# Planta_3_sobreamortiguada.net
KiCad netlist of a schematic drawn in EAGLE
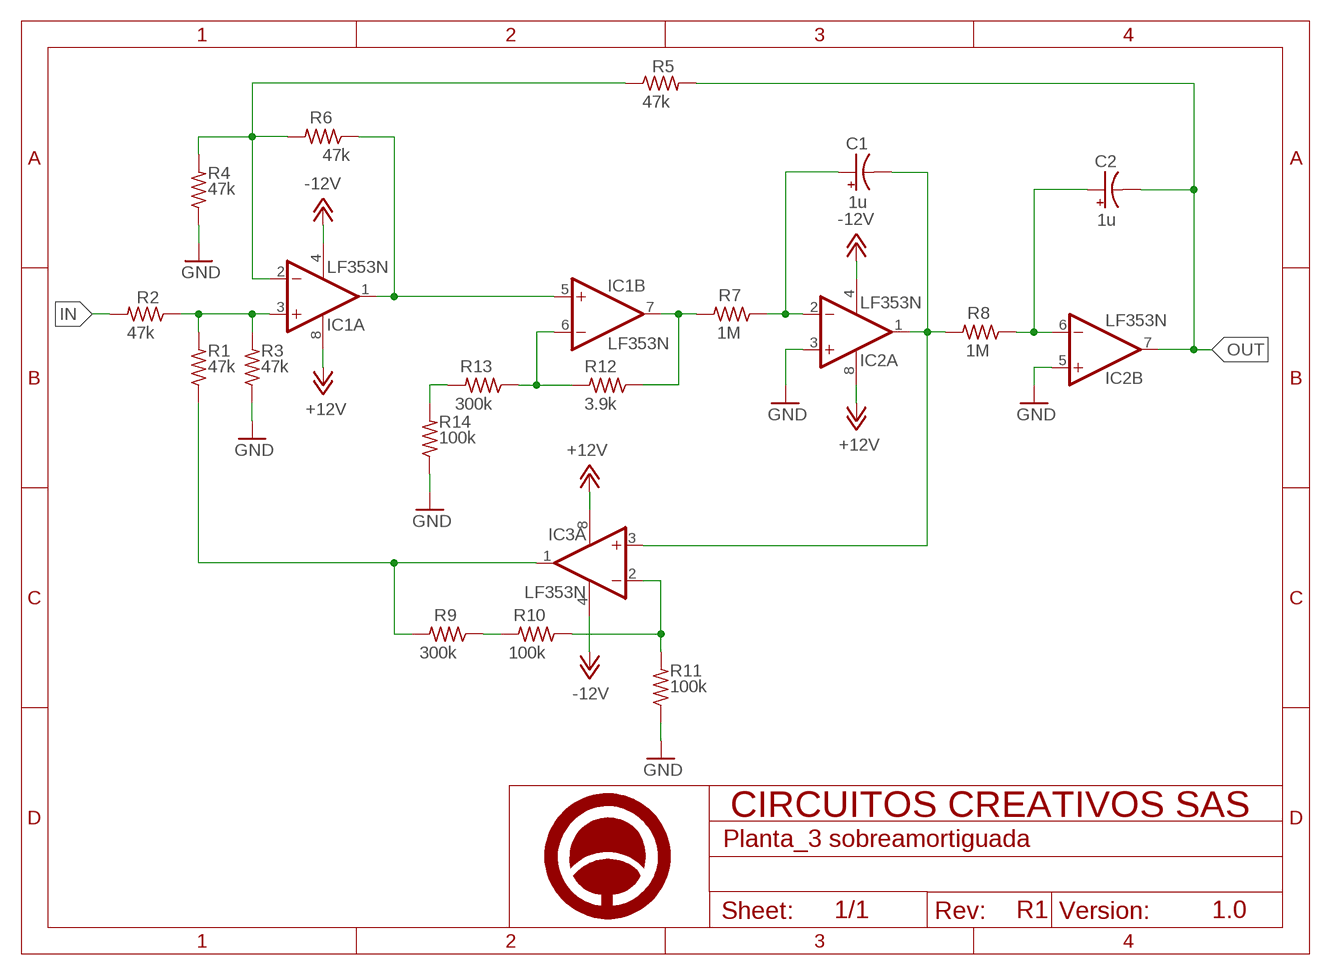
[diagram p0: schematic, sheet 1]

(export (version "E")
  (design (tool "Eeschema 10.0.6"))
  (components
    (comp (ref "C1")
      (value "1u")
      (footprint "eagle-import:E2-5")
      (libsource (lib "eagle-import") (part "CPOL-USE2-5"))
    )
    (comp (ref "C2")
      (value "1u")
      (footprint "eagle-import:E2-5")
      (libsource (lib "eagle-import") (part "CPOL-USE2-5"))
    )
    (comp (ref "F1")
      (value "A5_HORIZONTAL")
      (footprint "eagle-import:LOGO")
      (libsource (lib "eagle-import") (part "A5_HORIZONTAL"))
    )
    (comp (ref "IC1")
      (value "LF353N")
      (footprint "eagle-import:DIL08")
      (libsource (lib "eagle-import") (part "LF353N"))
    )
    (comp (ref "IC2")
      (value "LF353N")
      (footprint "eagle-import:DIL08")
      (libsource (lib "eagle-import") (part "LF353N"))
    )
    (comp (ref "IC3")
      (value "LF353N")
      (footprint "eagle-import:DIL08")
      (libsource (lib "eagle-import") (part "LF353N"))
    )
    (comp (ref "R1")
      (value "47k")
      (footprint "eagle-import:0204_7")
      (libsource (lib "eagle-import") (part "R-US_0204/7"))
    )
    (comp (ref "R2")
      (value "47k")
      (footprint "eagle-import:0204_7")
      (libsource (lib "eagle-import") (part "R-US_0204/7"))
    )
    (comp (ref "R3")
      (value "47k")
      (footprint "eagle-import:0204_7")
      (libsource (lib "eagle-import") (part "R-US_0204/7"))
    )
    (comp (ref "R4")
      (value "47k")
      (footprint "eagle-import:0204_7")
      (libsource (lib "eagle-import") (part "R-US_0204/7"))
    )
    (comp (ref "R5")
      (value "47k")
      (footprint "eagle-import:0204_7")
      (libsource (lib "eagle-import") (part "R-US_0204/7"))
    )
    (comp (ref "R6")
      (value "47k")
      (footprint "eagle-import:0204_7")
      (libsource (lib "eagle-import") (part "R-US_0204/7"))
    )
    (comp (ref "R7")
      (value "1M")
      (footprint "eagle-import:0204_7")
      (libsource (lib "eagle-import") (part "R-US_0204/7"))
    )
    (comp (ref "R8")
      (value "1M")
      (footprint "eagle-import:0204_7")
      (libsource (lib "eagle-import") (part "R-US_0204/7"))
    )
    (comp (ref "R9")
      (value "300k")
      (footprint "eagle-import:0204_7")
      (libsource (lib "eagle-import") (part "R-US_0204/7"))
    )
    (comp (ref "R10")
      (value "100k")
      (footprint "eagle-import:0204_7")
      (libsource (lib "eagle-import") (part "R-US_0204/7"))
    )
    (comp (ref "R11")
      (value "100k")
      (footprint "eagle-import:0204_7")
      (libsource (lib "eagle-import") (part "R-US_0204/7"))
    )
    (comp (ref "R12")
      (value "3.9k")
      (footprint "eagle-import:0204_7")
      (libsource (lib "eagle-import") (part "R-US_0204/7"))
    )
    (comp (ref "R13")
      (value "300k")
      (footprint "eagle-import:0204_7")
      (libsource (lib "eagle-import") (part "R-US_0204/7"))
    )
    (comp (ref "R14")
      (value "100k")
      (footprint "eagle-import:0204_7")
      (libsource (lib "eagle-import") (part "R-US_0204/7"))
    )
  )
  (nets
    (net (code "1") (name "+12V") (class "Default")
      (node (ref "IC1") (pin "8") (pinfunction "V+_8") (pintype "power_in"))
      (node (ref "IC2") (pin "8") (pinfunction "V+_8") (pintype "power_in"))
      (node (ref "IC3") (pin "8") (pinfunction "V+_8") (pintype "power_in"))
    )
    (net (code "2") (name "-12V") (class "Default")
      (node (ref "IC1") (pin "4") (pinfunction "V-_4") (pintype "power_in"))
      (node (ref "IC2") (pin "4") (pinfunction "V-_4") (pintype "power_in"))
      (node (ref "IC3") (pin "4") (pinfunction "V-_4") (pintype "power_in"))
    )
    (net (code "3") (name "GND") (class "Default")
      (node (ref "IC2") (pin "3") (pinfunction "+IN_3") (pintype "input"))
      (node (ref "IC2") (pin "5") (pinfunction "+IN_5") (pintype "input"))
      (node (ref "R11") (pin "1") (pinfunction "1_1") (pintype "passive"))
      (node (ref "R14") (pin "1") (pinfunction "1_1") (pintype "passive"))
      (node (ref "R3") (pin "1") (pinfunction "1_1") (pintype "passive"))
      (node (ref "R4") (pin "1") (pinfunction "1_1") (pintype "passive"))
    )
    (net (code "4") (name "IN") (class "Default")
      (node (ref "R2") (pin "2") (pinfunction "2_2") (pintype "passive"))
    )
    (net (code "5") (name "Net-(IC1A-+IN)") (class "Default")
      (node (ref "IC1") (pin "3") (pinfunction "+IN_3") (pintype "input"))
      (node (ref "R1") (pin "2") (pinfunction "2_2") (pintype "passive"))
      (node (ref "R2") (pin "1") (pinfunction "1_1") (pintype "passive"))
      (node (ref "R3") (pin "2") (pinfunction "2_2") (pintype "passive"))
    )
    (net (code "6") (name "Net-(IC1A--IN)") (class "Default")
      (node (ref "IC1") (pin "2") (pinfunction "-IN_2") (pintype "input"))
      (node (ref "R4") (pin "2") (pinfunction "2_2") (pintype "passive"))
      (node (ref "R5") (pin "1") (pinfunction "1_1") (pintype "passive"))
      (node (ref "R6") (pin "2") (pinfunction "2_2") (pintype "passive"))
    )
    (net (code "7") (name "Net-(IC1A-OUT)") (class "Default")
      (node (ref "IC1") (pin "1") (pinfunction "OUT_1") (pintype "output"))
      (node (ref "IC1") (pin "5") (pinfunction "+IN_5") (pintype "input"))
      (node (ref "R6") (pin "1") (pinfunction "1_1") (pintype "passive"))
    )
    (net (code "8") (name "Net-(IC1B--IN)") (class "Default")
      (node (ref "IC1") (pin "6") (pinfunction "-IN_6") (pintype "input"))
      (node (ref "R12") (pin "2") (pinfunction "2_2") (pintype "passive"))
      (node (ref "R13") (pin "1") (pinfunction "1_1") (pintype "passive"))
    )
    (net (code "9") (name "Net-(IC1B-OUT)") (class "Default")
      (node (ref "IC1") (pin "7") (pinfunction "OUT_7") (pintype "output"))
      (node (ref "R12") (pin "1") (pinfunction "1_1") (pintype "passive"))
      (node (ref "R7") (pin "2") (pinfunction "2_2") (pintype "passive"))
    )
    (net (code "10") (name "Net-(IC2A--IN)") (class "Default")
      (node (ref "C1") (pin "+") (pinfunction "+_+") (pintype "passive"))
      (node (ref "IC2") (pin "2") (pinfunction "-IN_2") (pintype "input"))
      (node (ref "R7") (pin "1") (pinfunction "1_1") (pintype "passive"))
    )
    (net (code "11") (name "Net-(IC2A-OUT)") (class "Default")
      (node (ref "C1") (pin "-") (pinfunction "-_-") (pintype "passive"))
      (node (ref "IC2") (pin "1") (pinfunction "OUT_1") (pintype "output"))
      (node (ref "IC3") (pin "3") (pinfunction "+IN_3") (pintype "input"))
      (node (ref "R8") (pin "2") (pinfunction "2_2") (pintype "passive"))
    )
    (net (code "12") (name "Net-(IC2B--IN)") (class "Default")
      (node (ref "C2") (pin "+") (pinfunction "+_+") (pintype "passive"))
      (node (ref "IC2") (pin "6") (pinfunction "-IN_6") (pintype "input"))
      (node (ref "R8") (pin "1") (pinfunction "1_1") (pintype "passive"))
    )
    (net (code "13") (name "Net-(IC3A--IN)") (class "Default")
      (node (ref "IC3") (pin "2") (pinfunction "-IN_2") (pintype "input"))
      (node (ref "R10") (pin "1") (pinfunction "1_1") (pintype "passive"))
      (node (ref "R11") (pin "2") (pinfunction "2_2") (pintype "passive"))
    )
    (net (code "14") (name "Net-(IC3A-OUT)") (class "Default")
      (node (ref "IC3") (pin "1") (pinfunction "OUT_1") (pintype "output"))
      (node (ref "R1") (pin "1") (pinfunction "1_1") (pintype "passive"))
      (node (ref "R9") (pin "2") (pinfunction "2_2") (pintype "passive"))
    )
    (net (code "15") (name "Net-(R10-Pad2)") (class "Default")
      (node (ref "R10") (pin "2") (pinfunction "2_2") (pintype "passive"))
      (node (ref "R9") (pin "1") (pinfunction "1_1") (pintype "passive"))
    )
    (net (code "16") (name "Net-(R13-Pad2)") (class "Default")
      (node (ref "R13") (pin "2") (pinfunction "2_2") (pintype "passive"))
      (node (ref "R14") (pin "2") (pinfunction "2_2") (pintype "passive"))
    )
    (net (code "17") (name "OUT") (class "Default")
      (node (ref "C2") (pin "-") (pinfunction "-_-") (pintype "passive"))
      (node (ref "IC2") (pin "7") (pinfunction "OUT_7") (pintype "output"))
      (node (ref "R5") (pin "2") (pinfunction "2_2") (pintype "passive"))
    )
  )
)
